# spi_dac.net
KiCad netlist of a schematic drawn in EAGLE
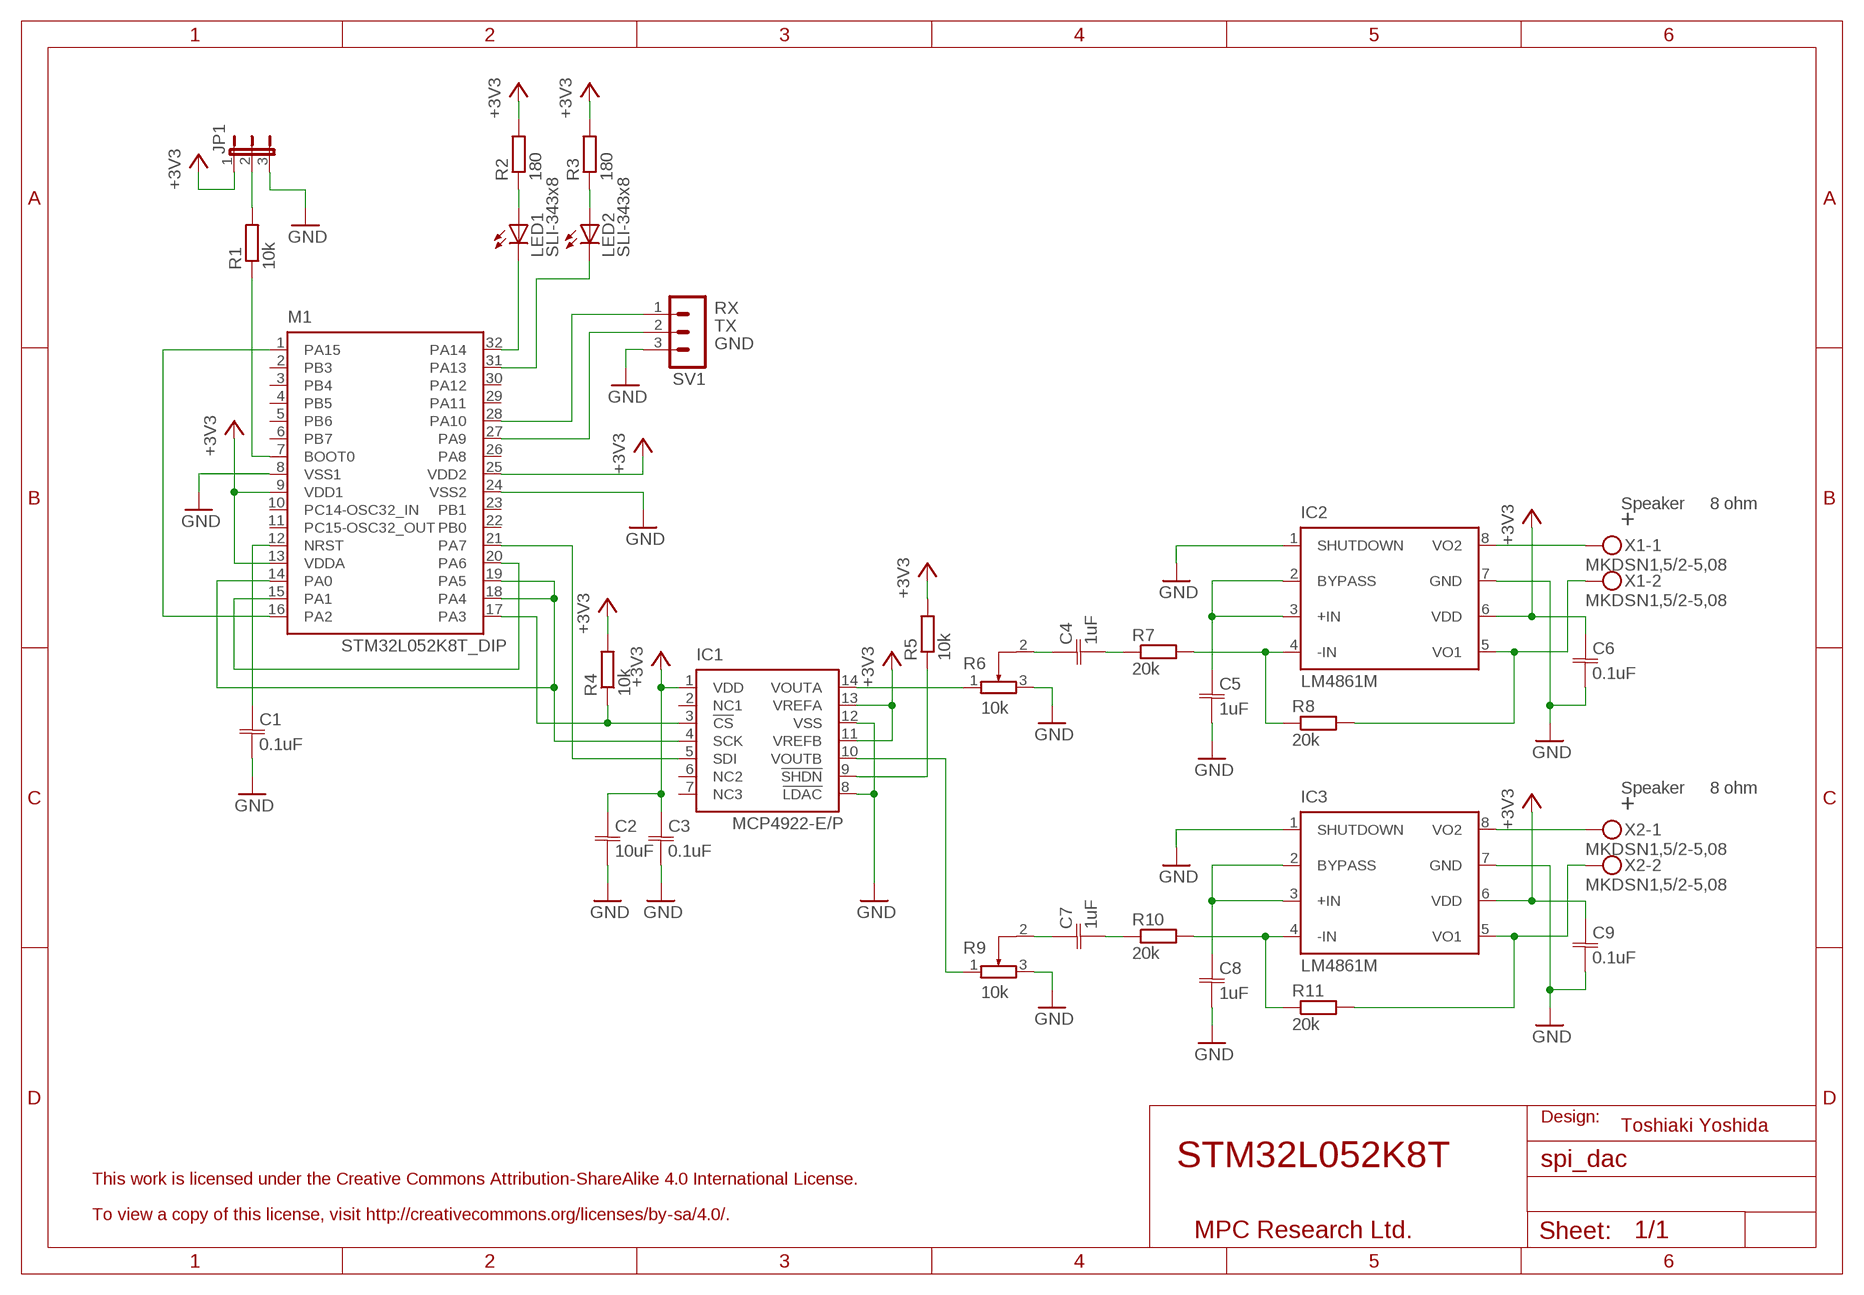
[diagram p0: schematic, sheet 1]

(export (version "E")
  (design (tool "Eeschema 10.0.6"))
  (components
    (comp (ref "C1")
      (value "0.1uF")
      (footprint "eagle-import:C050-024X044")
      (libsource (lib "eagle-import") (part "C-JIS050-024X044"))
    )
    (comp (ref "C2")
      (value "10uF")
      (footprint "eagle-import:C050-024X044")
      (libsource (lib "eagle-import") (part "C-JIS050-024X044"))
    )
    (comp (ref "C3")
      (value "0.1uF")
      (footprint "eagle-import:C050-024X044")
      (libsource (lib "eagle-import") (part "C-JIS050-024X044"))
    )
    (comp (ref "C4")
      (value "1uF")
      (footprint "eagle-import:C050-024X044")
      (libsource (lib "eagle-import") (part "C-JIS050-024X044"))
    )
    (comp (ref "C5")
      (value "1uF")
      (footprint "eagle-import:C050-024X044")
      (libsource (lib "eagle-import") (part "C-JIS050-024X044"))
    )
    (comp (ref "C6")
      (value "0.1uF")
      (footprint "eagle-import:C050-024X044")
      (libsource (lib "eagle-import") (part "C-JIS050-024X044"))
    )
    (comp (ref "C7")
      (value "1uF")
      (footprint "eagle-import:C050-024X044")
      (libsource (lib "eagle-import") (part "C-JIS050-024X044"))
    )
    (comp (ref "C8")
      (value "1uF")
      (footprint "eagle-import:C050-024X044")
      (libsource (lib "eagle-import") (part "C-JIS050-024X044"))
    )
    (comp (ref "C9")
      (value "0.1uF")
      (footprint "eagle-import:C050-024X044")
      (libsource (lib "eagle-import") (part "C-JIS050-024X044"))
    )
    (comp (ref "IC1")
      (value "MCP4922-E/P")
      (footprint "eagle-import:DIL14")
      (libsource (lib "eagle-import") (part "MCP492-E/P2"))
    )
    (comp (ref "IC2")
      (value "LM4861M")
      (footprint "eagle-import:SO-08")
      (libsource (lib "eagle-import") (part "LM4861M"))
    )
    (comp (ref "IC3")
      (value "LM4861M")
      (footprint "eagle-import:SO-08")
      (libsource (lib "eagle-import") (part "LM4861M"))
    )
    (comp (ref "JP1")
      (value "JP2E")
      (footprint "eagle-import:JP2")
      (libsource (lib "eagle-import") (part "JP2E"))
    )
    (comp (ref "LED1")
      (value "SLI-343x8")
      (footprint "eagle-import:LED3MM")
      (libsource (lib "eagle-import") (part "LED3MM"))
    )
    (comp (ref "LED2")
      (value "SLI-343x8")
      (footprint "eagle-import:LED3MM")
      (libsource (lib "eagle-import") (part "LED3MM"))
    )
    (comp (ref "M1")
      (value "STM32L052K8T_DIP")
      (footprint "eagle-import:DIP32")
      (libsource (lib "eagle-import") (part "STM32L052K8T_DIP"))
    )
    (comp (ref "R1")
      (value "10k")
      (footprint "eagle-import:0207_2V")
      (libsource (lib "eagle-import") (part "R-EU_0207/2V"))
    )
    (comp (ref "R2")
      (value "180")
      (footprint "eagle-import:0207_2V")
      (libsource (lib "eagle-import") (part "R-EU_0207/2V"))
    )
    (comp (ref "R3")
      (value "180")
      (footprint "eagle-import:0207_2V")
      (libsource (lib "eagle-import") (part "R-EU_0207/2V"))
    )
    (comp (ref "R4")
      (value "10k")
      (footprint "eagle-import:0207_2V")
      (libsource (lib "eagle-import") (part "R-EU_0207/2V"))
    )
    (comp (ref "R5")
      (value "10k")
      (footprint "eagle-import:0207_2V")
      (libsource (lib "eagle-import") (part "R-EU_0207/2V"))
    )
    (comp (ref "R6")
      (value "10k")
      (footprint "eagle-import:TSR-3386T")
      (libsource (lib "eagle-import") (part "TSR-3386T-EY5"))
    )
    (comp (ref "R7")
      (value "20k")
      (footprint "eagle-import:0207_2V")
      (libsource (lib "eagle-import") (part "R-EU_0207/2V"))
    )
    (comp (ref "R8")
      (value "20k")
      (footprint "eagle-import:0207_10")
      (libsource (lib "eagle-import") (part "R-EU_0207/10"))
    )
    (comp (ref "R9")
      (value "10k")
      (footprint "eagle-import:TSR-3386T")
      (libsource (lib "eagle-import") (part "TSR-3386T-EY5"))
    )
    (comp (ref "R10")
      (value "20k")
      (footprint "eagle-import:0207_2V")
      (libsource (lib "eagle-import") (part "R-EU_0207/2V"))
    )
    (comp (ref "R11")
      (value "20k")
      (footprint "eagle-import:0207_10")
      (libsource (lib "eagle-import") (part "R-EU_0207/10"))
    )
    (comp (ref "SV1")
      (value "MA03-1")
      (footprint "eagle-import:MA03-1")
      (libsource (lib "eagle-import") (part "MA03-1"))
    )
    (comp (ref "X1")
      (value "MKDSN1,5/2-5,08")
      (footprint "eagle-import:MKDSN1,5_2-5,08")
      (libsource (lib "eagle-import") (part "MKDSN1,5/2-5,08"))
    )
    (comp (ref "X2")
      (value "MKDSN1,5/2-5,08")
      (footprint "eagle-import:MKDSN1,5_2-5,08")
      (libsource (lib "eagle-import") (part "MKDSN1,5/2-5,08"))
    )
  )
  (nets
    (net (code "1") (name "+3V3") (class "Default")
      (node (ref "C2") (pin "1") (pinfunction "1_1") (pintype "passive"))
      (node (ref "C3") (pin "1") (pinfunction "1_1") (pintype "passive"))
      (node (ref "C6") (pin "1") (pinfunction "1_1") (pintype "passive"))
      (node (ref "C9") (pin "1") (pinfunction "1_1") (pintype "passive"))
      (node (ref "IC1") (pin "1") (pinfunction "VDD_1") (pintype "power_in"))
      (node (ref "IC1") (pin "11") (pinfunction "VREFB_11") (pintype "input"))
      (node (ref "IC1") (pin "13") (pinfunction "VREFA_13") (pintype "input"))
      (node (ref "IC2") (pin "6") (pinfunction "VDD_6") (pintype "power_in"))
      (node (ref "IC3") (pin "6") (pinfunction "VDD_6") (pintype "power_in"))
      (node (ref "JP1") (pin "1") (pinfunction "1_1") (pintype "passive"))
      (node (ref "M1") (pin "13") (pinfunction "VDDA_13") (pintype "power_in"))
      (node (ref "M1") (pin "25") (pinfunction "VDD2_25") (pintype "bidirectional"))
      (node (ref "M1") (pin "9") (pinfunction "VDD1_9") (pintype "power_in"))
      (node (ref "R2") (pin "2") (pinfunction "2_2") (pintype "passive"))
      (node (ref "R3") (pin "2") (pinfunction "2_2") (pintype "passive"))
      (node (ref "R4") (pin "2") (pinfunction "2_2") (pintype "passive"))
      (node (ref "R5") (pin "2") (pinfunction "2_2") (pintype "passive"))
    )
    (net (code "2") (name "GND") (class "Default")
      (node (ref "C1") (pin "2") (pinfunction "2_2") (pintype "passive"))
      (node (ref "C2") (pin "2") (pinfunction "2_2") (pintype "passive"))
      (node (ref "C3") (pin "2") (pinfunction "2_2") (pintype "passive"))
      (node (ref "C5") (pin "2") (pinfunction "2_2") (pintype "passive"))
      (node (ref "C6") (pin "2") (pinfunction "2_2") (pintype "passive"))
      (node (ref "C8") (pin "2") (pinfunction "2_2") (pintype "passive"))
      (node (ref "C9") (pin "2") (pinfunction "2_2") (pintype "passive"))
      (node (ref "IC1") (pin "12") (pinfunction "VSS_12") (pintype "power_in"))
      (node (ref "IC1") (pin "8") (pinfunction "~{LDAC}_8") (pintype "input"))
      (node (ref "IC2") (pin "1") (pinfunction "SHUTDOWN_1") (pintype "input"))
      (node (ref "IC2") (pin "7") (pinfunction "GND_7") (pintype "power_in"))
      (node (ref "IC3") (pin "1") (pinfunction "SHUTDOWN_1") (pintype "input"))
      (node (ref "IC3") (pin "7") (pinfunction "GND_7") (pintype "power_in"))
      (node (ref "JP1") (pin "3") (pinfunction "3_3") (pintype "passive"))
      (node (ref "M1") (pin "24") (pinfunction "VSS2_24") (pintype "power_in"))
      (node (ref "M1") (pin "8") (pinfunction "VSS1_8") (pintype "power_in"))
      (node (ref "R6") (pin "3") (pinfunction "3_3") (pintype "passive"))
      (node (ref "R9") (pin "3") (pinfunction "3_3") (pintype "passive"))
      (node (ref "SV1") (pin "3") (pinfunction "3_3") (pintype "passive"))
    )
    (net (code "3") (name "Net-(C4-Pad1)") (class "Default")
      (node (ref "C4") (pin "1") (pinfunction "1_1") (pintype "passive"))
      (node (ref "R6") (pin "2") (pinfunction "2_2") (pintype "passive"))
    )
    (net (code "4") (name "Net-(C4-Pad2)") (class "Default")
      (node (ref "C4") (pin "2") (pinfunction "2_2") (pintype "passive"))
      (node (ref "R7") (pin "1") (pinfunction "1_1") (pintype "passive"))
    )
    (net (code "5") (name "Net-(C7-Pad1)") (class "Default")
      (node (ref "C7") (pin "1") (pinfunction "1_1") (pintype "passive"))
      (node (ref "R9") (pin "2") (pinfunction "2_2") (pintype "passive"))
    )
    (net (code "6") (name "Net-(C7-Pad2)") (class "Default")
      (node (ref "C7") (pin "2") (pinfunction "2_2") (pintype "passive"))
      (node (ref "R10") (pin "1") (pinfunction "1_1") (pintype "passive"))
    )
    (net (code "7") (name "Net-(IC1-SCK)") (class "Default")
      (node (ref "IC1") (pin "4") (pinfunction "SCK_4") (pintype "input"))
      (node (ref "M1") (pin "14") (pinfunction "PA0_14") (pintype "bidirectional"))
      (node (ref "M1") (pin "18") (pinfunction "PA4_18") (pintype "bidirectional"))
      (node (ref "M1") (pin "19") (pinfunction "PA5_19") (pintype "bidirectional"))
    )
    (net (code "8") (name "Net-(IC1-SDI)") (class "Default")
      (node (ref "IC1") (pin "5") (pinfunction "SDI_5") (pintype "input"))
      (node (ref "M1") (pin "21") (pinfunction "PA7_21") (pintype "bidirectional"))
    )
    (net (code "9") (name "Net-(IC1-VOUTA)") (class "Default")
      (node (ref "IC1") (pin "14") (pinfunction "VOUTA_14") (pintype "output"))
      (node (ref "R6") (pin "1") (pinfunction "1_1") (pintype "passive"))
    )
    (net (code "10") (name "Net-(IC1-VOUTB)") (class "Default")
      (node (ref "IC1") (pin "10") (pinfunction "VOUTB_10") (pintype "output"))
      (node (ref "R9") (pin "1") (pinfunction "1_1") (pintype "passive"))
    )
    (net (code "11") (name "Net-(IC1-~{CS})") (class "Default")
      (node (ref "IC1") (pin "3") (pinfunction "~{CS}_3") (pintype "input"))
      (node (ref "M1") (pin "17") (pinfunction "PA3_17") (pintype "bidirectional"))
      (node (ref "R4") (pin "1") (pinfunction "1_1") (pintype "passive"))
    )
    (net (code "12") (name "Net-(IC1-~{SHDN})") (class "Default")
      (node (ref "IC1") (pin "9") (pinfunction "~{SHDN}_9") (pintype "input"))
      (node (ref "R5") (pin "1") (pinfunction "1_1") (pintype "passive"))
    )
    (net (code "13") (name "Net-(IC2-+IN)") (class "Default")
      (node (ref "C5") (pin "1") (pinfunction "1_1") (pintype "passive"))
      (node (ref "IC2") (pin "2") (pinfunction "BYPASS_2") (pintype "passive"))
      (node (ref "IC2") (pin "3") (pinfunction "+IN_3") (pintype "input"))
    )
    (net (code "14") (name "Net-(IC2--IN)") (class "Default")
      (node (ref "IC2") (pin "4") (pinfunction "-IN_4") (pintype "input"))
      (node (ref "R7") (pin "2") (pinfunction "2_2") (pintype "passive"))
      (node (ref "R8") (pin "1") (pinfunction "1_1") (pintype "passive"))
    )
    (net (code "15") (name "Net-(IC2-VO1)") (class "Default")
      (node (ref "IC2") (pin "5") (pinfunction "VO1_5") (pintype "output"))
      (node (ref "R8") (pin "2") (pinfunction "2_2") (pintype "passive"))
      (node (ref "X1") (pin "2") (pinfunction "KL_2") (pintype "passive"))
    )
    (net (code "16") (name "Net-(IC2-VO2)") (class "Default")
      (node (ref "IC2") (pin "8") (pinfunction "VO2_8") (pintype "output"))
      (node (ref "X1") (pin "1") (pinfunction "KL_1") (pintype "passive"))
    )
    (net (code "17") (name "Net-(IC3-+IN)") (class "Default")
      (node (ref "C8") (pin "1") (pinfunction "1_1") (pintype "passive"))
      (node (ref "IC3") (pin "2") (pinfunction "BYPASS_2") (pintype "passive"))
      (node (ref "IC3") (pin "3") (pinfunction "+IN_3") (pintype "input"))
    )
    (net (code "18") (name "Net-(IC3--IN)") (class "Default")
      (node (ref "IC3") (pin "4") (pinfunction "-IN_4") (pintype "input"))
      (node (ref "R10") (pin "2") (pinfunction "2_2") (pintype "passive"))
      (node (ref "R11") (pin "1") (pinfunction "1_1") (pintype "passive"))
    )
    (net (code "19") (name "Net-(IC3-VO1)") (class "Default")
      (node (ref "IC3") (pin "5") (pinfunction "VO1_5") (pintype "output"))
      (node (ref "R11") (pin "2") (pinfunction "2_2") (pintype "passive"))
      (node (ref "X2") (pin "2") (pinfunction "KL_2") (pintype "passive"))
    )
    (net (code "20") (name "Net-(IC3-VO2)") (class "Default")
      (node (ref "IC3") (pin "8") (pinfunction "VO2_8") (pintype "output"))
      (node (ref "X2") (pin "1") (pinfunction "KL_1") (pintype "passive"))
    )
    (net (code "21") (name "Net-(JP1-Pad2)") (class "Default")
      (node (ref "JP1") (pin "2") (pinfunction "2_2") (pintype "passive"))
      (node (ref "R1") (pin "2") (pinfunction "2_2") (pintype "passive"))
    )
    (net (code "22") (name "Net-(LED1-C)") (class "Default")
      (node (ref "LED1") (pin "K") (pinfunction "C_K") (pintype "passive"))
      (node (ref "M1") (pin "32") (pinfunction "PA14_32") (pintype "bidirectional"))
    )
    (net (code "23") (name "Net-(LED1-PadA)") (class "Default")
      (node (ref "LED1") (pin "A") (pinfunction "A_A") (pintype "passive"))
      (node (ref "R2") (pin "1") (pinfunction "1_1") (pintype "passive"))
    )
    (net (code "24") (name "Net-(LED2-C)") (class "Default")
      (node (ref "LED2") (pin "K") (pinfunction "C_K") (pintype "passive"))
      (node (ref "M1") (pin "31") (pinfunction "PA13_31") (pintype "bidirectional"))
    )
    (net (code "25") (name "Net-(LED2-PadA)") (class "Default")
      (node (ref "LED2") (pin "A") (pinfunction "A_A") (pintype "passive"))
      (node (ref "R3") (pin "1") (pinfunction "1_1") (pintype "passive"))
    )
    (net (code "26") (name "Net-(M1-BOOT0)") (class "Default")
      (node (ref "M1") (pin "7") (pinfunction "BOOT0_7") (pintype "bidirectional"))
      (node (ref "R1") (pin "1") (pinfunction "1_1") (pintype "passive"))
    )
    (net (code "27") (name "Net-(M1-NRST)") (class "Default")
      (node (ref "C1") (pin "1") (pinfunction "1_1") (pintype "passive"))
      (node (ref "M1") (pin "12") (pinfunction "NRST_12") (pintype "bidirectional"))
    )
    (net (code "28") (name "Net-(M1-PA1)") (class "Default")
      (node (ref "M1") (pin "15") (pinfunction "PA1_15") (pintype "bidirectional"))
      (node (ref "M1") (pin "20") (pinfunction "PA6_20") (pintype "bidirectional"))
    )
    (net (code "29") (name "Net-(M1-PA9)") (class "Default")
      (node (ref "M1") (pin "27") (pinfunction "PA9_27") (pintype "bidirectional"))
      (node (ref "SV1") (pin "2") (pinfunction "2_2") (pintype "passive"))
    )
    (net (code "30") (name "Net-(M1-PA10)") (class "Default")
      (node (ref "M1") (pin "28") (pinfunction "PA10_28") (pintype "bidirectional"))
      (node (ref "SV1") (pin "1") (pinfunction "1_1") (pintype "passive"))
    )
    (net (code "31") (name "Net-(M1-PA15)") (class "Default")
      (node (ref "M1") (pin "1") (pinfunction "PA15_1") (pintype "bidirectional"))
      (node (ref "M1") (pin "16") (pinfunction "PA2_16") (pintype "bidirectional"))
    )
    (net (code "32") (name "unconnected-(IC1-NC1-Pad2)") (class "Default")
      (node (ref "IC1") (pin "2") (pinfunction "NC1_2") (pintype "passive"))
    )
    (net (code "33") (name "unconnected-(IC1-NC2-Pad6)") (class "Default")
      (node (ref "IC1") (pin "6") (pinfunction "NC2_6") (pintype "passive"))
    )
    (net (code "34") (name "unconnected-(IC1-NC3-Pad7)") (class "Default")
      (node (ref "IC1") (pin "7") (pinfunction "NC3_7") (pintype "passive"))
    )
    (net (code "35") (name "unconnected-(M1-PA8-Pad26)") (class "Default")
      (node (ref "M1") (pin "26") (pinfunction "PA8_26") (pintype "bidirectional"))
    )
    (net (code "36") (name "unconnected-(M1-PA11-Pad29)") (class "Default")
      (node (ref "M1") (pin "29") (pinfunction "PA11_29") (pintype "bidirectional"))
    )
    (net (code "37") (name "unconnected-(M1-PA12-Pad30)") (class "Default")
      (node (ref "M1") (pin "30") (pinfunction "PA12_30") (pintype "bidirectional"))
    )
    (net (code "38") (name "unconnected-(M1-PB0-Pad22)") (class "Default")
      (node (ref "M1") (pin "22") (pinfunction "PB0_22") (pintype "bidirectional"))
    )
    (net (code "39") (name "unconnected-(M1-PB1-Pad23)") (class "Default")
      (node (ref "M1") (pin "23") (pinfunction "PB1_23") (pintype "bidirectional"))
    )
    (net (code "40") (name "unconnected-(M1-PB3-Pad2)") (class "Default")
      (node (ref "M1") (pin "2") (pinfunction "PB3_2") (pintype "bidirectional"))
    )
    (net (code "41") (name "unconnected-(M1-PB4-Pad3)") (class "Default")
      (node (ref "M1") (pin "3") (pinfunction "PB4_3") (pintype "bidirectional"))
    )
    (net (code "42") (name "unconnected-(M1-PB5-Pad4)") (class "Default")
      (node (ref "M1") (pin "4") (pinfunction "PB5_4") (pintype "bidirectional"))
    )
    (net (code "43") (name "unconnected-(M1-PB6-Pad5)") (class "Default")
      (node (ref "M1") (pin "5") (pinfunction "PB6_5") (pintype "bidirectional"))
    )
    (net (code "44") (name "unconnected-(M1-PB7-Pad6)") (class "Default")
      (node (ref "M1") (pin "6") (pinfunction "PB7_6") (pintype "bidirectional"))
    )
    (net (code "45") (name "unconnected-(M1-PC14-OSC32_IN-Pad10)") (class "Default")
      (node (ref "M1") (pin "10") (pinfunction "PC14-OSC32_IN_10") (pintype "bidirectional"))
    )
    (net (code "46") (name "unconnected-(M1-PC15-OSC32_OUT-Pad11)") (class "Default")
      (node (ref "M1") (pin "11") (pinfunction "PC15-OSC32_OUT_11") (pintype "bidirectional"))
    )
  )
)
